# Sheet1.net
KiCad netlist of a schematic drawn in Altium Designer
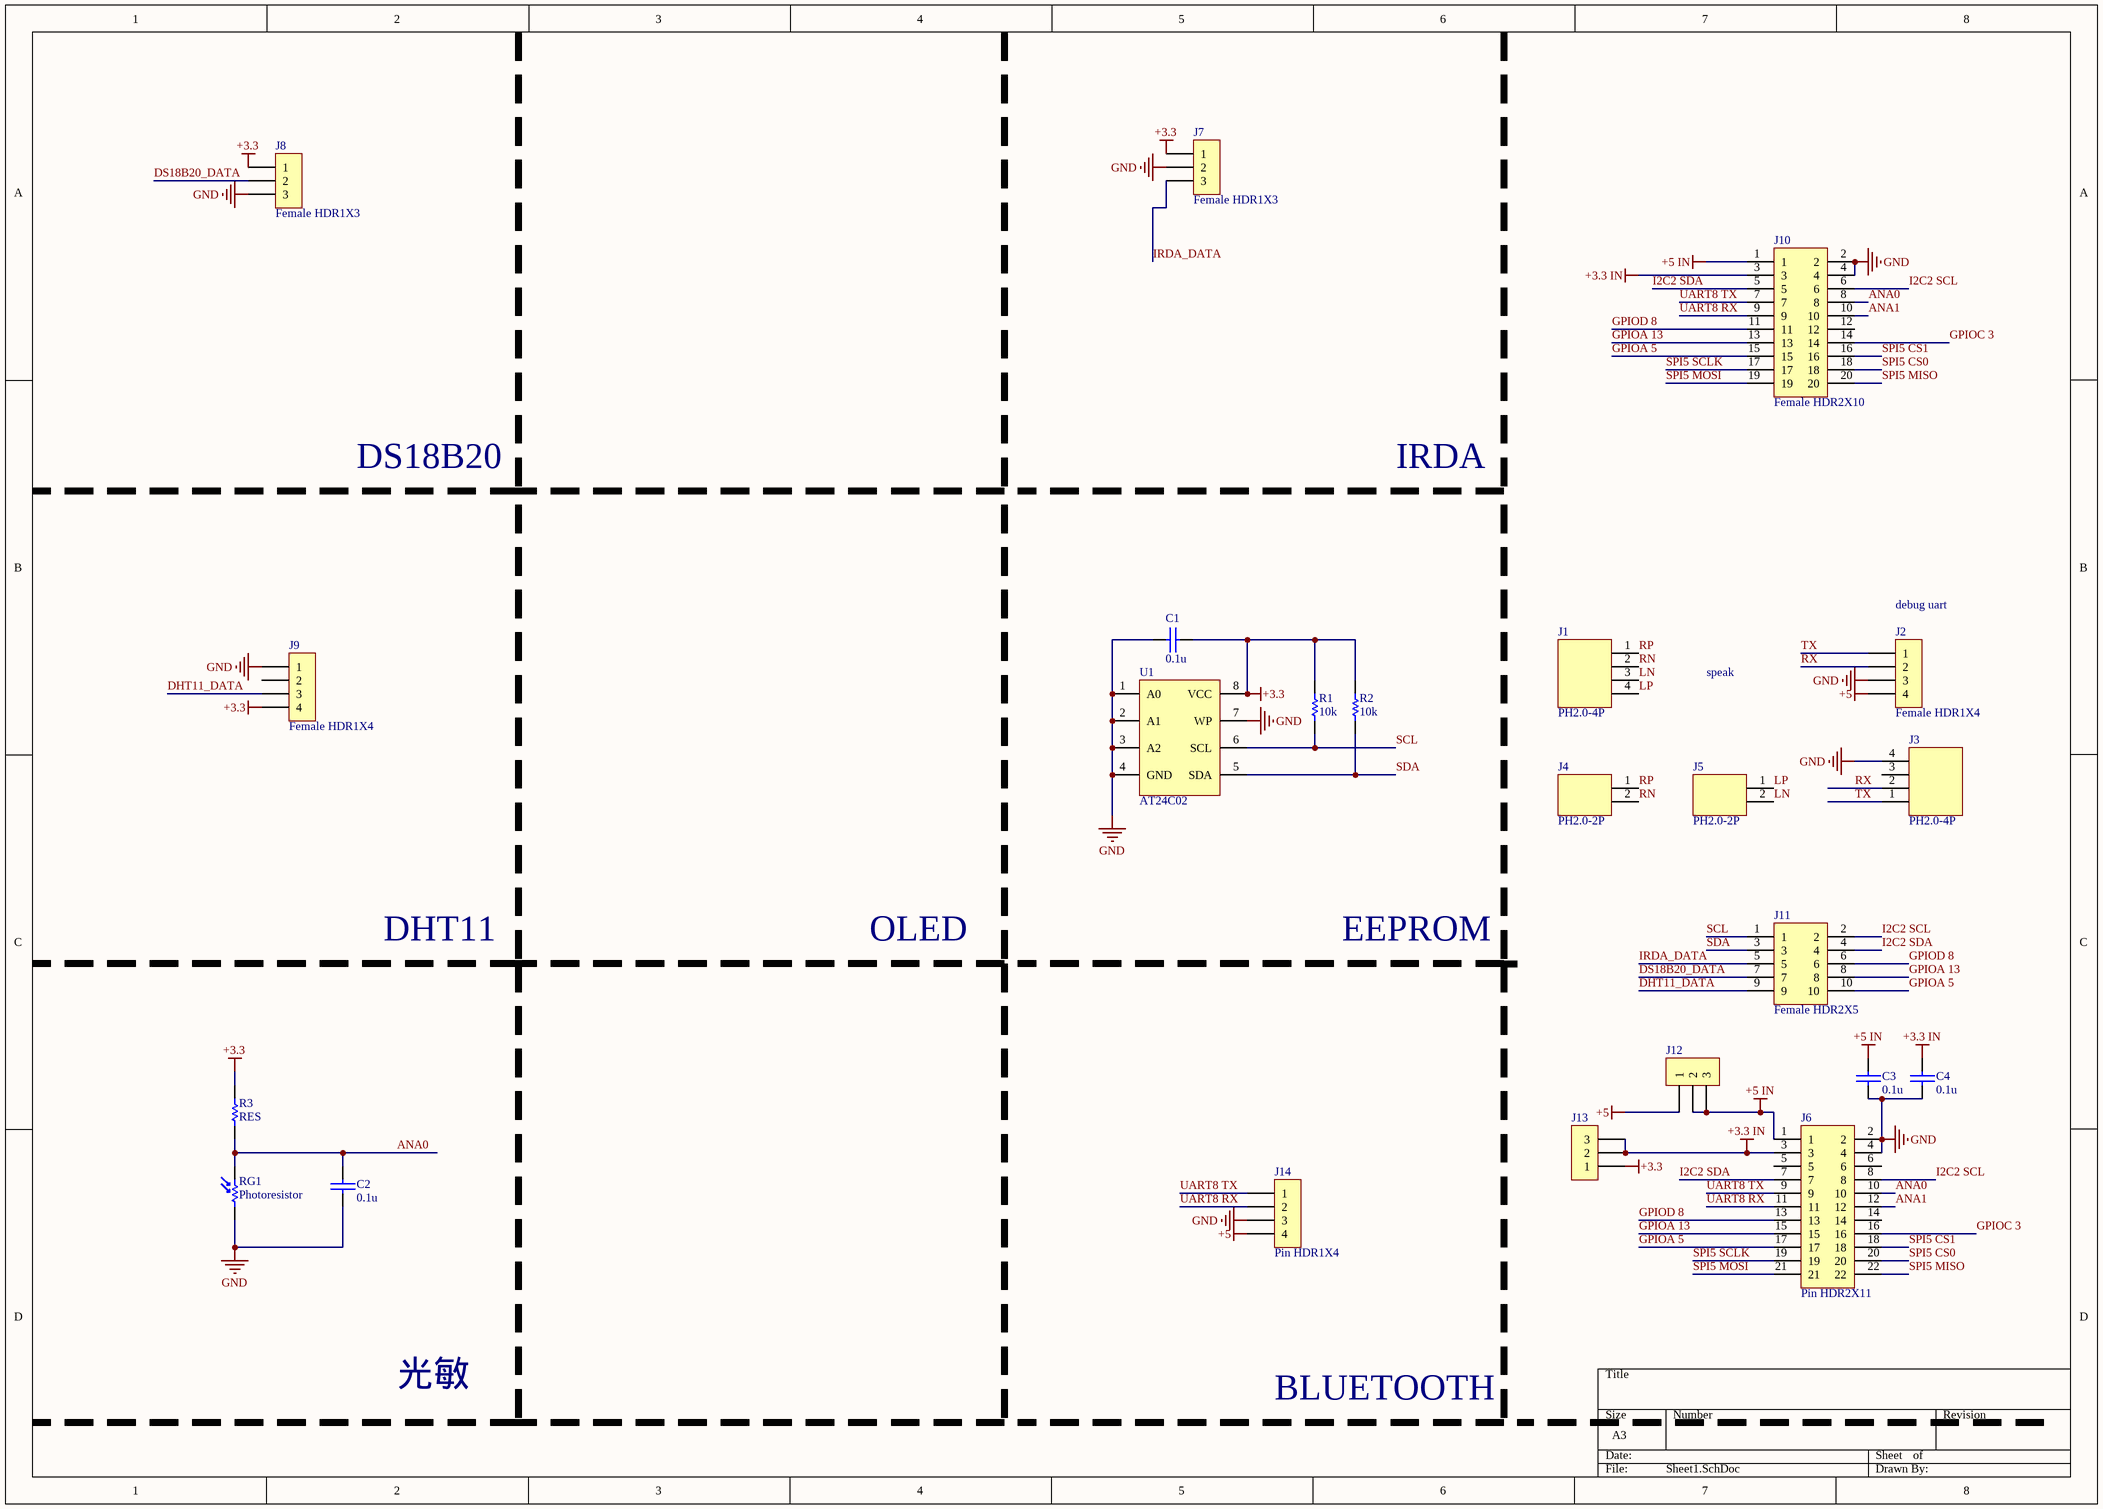
[diagram p0: Sheet1.SchDoc]

(export (version "E")
  (design (tool "Eeschema 10.0.6"))
  (components
    (comp (ref "C1")
      (value "0.1u")
      (footprint "0805C")
      (description "无极性电容")
      (libsource (lib "常用元件-电容") (part "CAP"))
    )
    (comp (ref "C2")
      (value "0.1u")
      (footprint "0805C")
      (description "无极性电容")
      (libsource (lib "常用元件-电容") (part "CAP"))
    )
    (comp (ref "C3")
      (value "0.1u")
      (footprint "0805C")
      (description "无极性电容")
      (libsource (lib "常用元件-电容") (part "CAP"))
    )
    (comp (ref "C4")
      (value "0.1u")
      (footprint "0805C")
      (description "无极性电容")
      (libsource (lib "常用元件-电容") (part "CAP"))
    )
    (comp (ref "J1") (value "PH2.0-4P") (footprint "PH2.0-4P") (libsource (lib "") (part "PH2.0-4P_1")))
    (comp (ref "J2")
      (value "Female HDR1X4")
      (footprint "Fe-HDR1X4/2.54-S")
      (libsource (lib "常用元件-排母") (part "Female HDR1X4"))
    )
    (comp (ref "J3") (value "PH2.0-4P") (footprint "PH2.0-4P") (libsource (lib "插接类-PH") (part "PH2.0-4P")))
    (comp (ref "J4") (value "PH2.0-2P") (footprint "PH2.0-2P") (libsource (lib "插接类-PH") (part "PH2.0-2P")))
    (comp (ref "J5") (value "PH2.0-2P") (footprint "PH2.0-2P") (libsource (lib "插接类-PH") (part "PH2.0-2P")))
    (comp (ref "J6")
      (value "Pin HDR2X11")
      (footprint "HDR-TH_22P-P2.00-V-F-R2-C11-S2.00")
      (libsource (lib "常用元件-排针") (part "Pin HDR2X11"))
    )
    (comp (ref "J7")
      (value "Female HDR1X3")
      (footprint "Fe-HDR1X3/2.54-S")
      (libsource (lib "") (part "Female HDR1X3_1"))
    )
    (comp (ref "J8")
      (value "Female HDR1X3")
      (footprint "Fe-HDR1X3/2.54-S")
      (libsource (lib "") (part "Female HDR1X3_1"))
    )
    (comp (ref "J9")
      (value "Female HDR1X4")
      (footprint "Fe-HDR1X4/2.54-S")
      (libsource (lib "常用元件-排母") (part "Female HDR1X4"))
    )
    (comp (ref "J10")
      (value "Female HDR2X10")
      (footprint "Fe-HDR2X10/2.54-S")
      (libsource (lib "常用元件-排母") (part "Female HDR2X10"))
    )
    (comp (ref "J11")
      (value "Female HDR2X5")
      (footprint "Fe-HDR2X5/2.54-S")
      (libsource (lib "常用元件-排母") (part "Female HDR2X5"))
    )
    (comp (ref "J12")
      (value "Female HDR1X3")
      (footprint "Fe-HDR1X3/2.54-S")
      (libsource (lib "") (part "Female HDR1X3_2"))
    )
    (comp (ref "J13")
      (value "Female HDR1X3")
      (footprint "Fe-HDR1X3/2.54-S")
      (libsource (lib "常用元件-排母") (part "Female HDR1X3"))
    )
    (comp (ref "J14")
      (value "Pin HDR1X4")
      (footprint "Pin HDR1X4/2.54mm-S")
      (libsource (lib "常用元件-排针") (part "Pin HDR1X4"))
    )
    (comp (ref "R1") (value "10k") (footprint "0805R") (libsource (lib "常用元件-电阻") (part "RES")))
    (comp (ref "R2") (value "10k") (footprint "0805R") (libsource (lib "常用元件-电阻") (part "RES")))
    (comp (ref "R3") (value "RES") (footprint "0805R") (libsource (lib "常用元件-电阻") (part "RES")))
    (comp (ref "RG1")
      (value "Photoresistor")
      (footprint "Photoresistor")
      (description "光敏电阻")
      (libsource (lib "常用元件-电阻") (part "Photoresistor"))
    )
    (comp (ref "U1") (value "AT24C02") (footprint "SOP8") (libsource (lib "芯片-未分类IC") (part "AT24C02")))
  )
  (nets
    (net (code "1") (name "+3.3") (class "Default")
      (node (ref "C1") (pin "2") (pinfunction "2_2") (pintype "passive"))
      (node (ref "J13") (pin "1") (pinfunction "1_1") (pintype "passive"))
      (node (ref "J7") (pin "1") (pinfunction "1_1") (pintype "passive"))
      (node (ref "J8") (pin "1") (pinfunction "1_1") (pintype "passive"))
      (node (ref "J9") (pin "4") (pinfunction "4_4") (pintype "passive"))
      (node (ref "R1") (pin "2") (pinfunction "2_2") (pintype "passive"))
      (node (ref "R2") (pin "2") (pinfunction "2_2") (pintype "passive"))
      (node (ref "R3") (pin "2") (pinfunction "2_2") (pintype "passive"))
      (node (ref "U1") (pin "8") (pinfunction "VCC_8") (pintype "passive"))
    )
    (net (code "2") (name "+3.3 IN") (class "Default")
      (node (ref "C4") (pin "2") (pinfunction "2_2") (pintype "passive"))
      (node (ref "J10") (pin "3") (pinfunction "3_3") (pintype "passive"))
      (node (ref "J13") (pin "2") (pinfunction "2_2") (pintype "passive"))
      (node (ref "J13") (pin "3") (pinfunction "3_3") (pintype "passive"))
      (node (ref "J6") (pin "3") (pinfunction "3_3") (pintype "passive"))
    )
    (net (code "3") (name "+5") (class "Default")
      (node (ref "J12") (pin "1") (pinfunction "1_1") (pintype "passive"))
      (node (ref "J14") (pin "4") (pinfunction "4_4") (pintype "passive"))
      (node (ref "J2") (pin "4") (pinfunction "4_4") (pintype "passive"))
    )
    (net (code "4") (name "+5 IN") (class "Default")
      (node (ref "C3") (pin "2") (pinfunction "2_2") (pintype "passive"))
      (node (ref "J10") (pin "1") (pinfunction "1_1") (pintype "passive"))
      (node (ref "J12") (pin "2") (pinfunction "2_2") (pintype "passive"))
      (node (ref "J12") (pin "3") (pinfunction "3_3") (pintype "passive"))
      (node (ref "J6") (pin "1") (pinfunction "1_1") (pintype "passive"))
    )
    (net (code "5") (name "/ANA0") (class "Default")
      (node (ref "C2") (pin "2") (pinfunction "2_2") (pintype "passive"))
      (node (ref "J10") (pin "8") (pinfunction "8_8") (pintype "passive"))
      (node (ref "J6") (pin "10") (pinfunction "10_10") (pintype "passive"))
      (node (ref "R3") (pin "1") (pinfunction "1_1") (pintype "passive"))
      (node (ref "RG1") (pin "2") (pinfunction "2_2") (pintype "passive"))
    )
    (net (code "6") (name "/ANA1") (class "Default")
      (node (ref "J10") (pin "10") (pinfunction "10_10") (pintype "passive"))
      (node (ref "J6") (pin "12") (pinfunction "12_12") (pintype "passive"))
    )
    (net (code "7") (name "/DHT11_DATA") (class "Default")
      (node (ref "J11") (pin "9") (pinfunction "9_9") (pintype "passive"))
      (node (ref "J9") (pin "3") (pinfunction "3_3") (pintype "passive"))
    )
    (net (code "8") (name "/DS18B20_DATA") (class "Default")
      (node (ref "J11") (pin "7") (pinfunction "7_7") (pintype "passive"))
      (node (ref "J8") (pin "2") (pinfunction "2_2") (pintype "passive"))
    )
    (net (code "9") (name "/GPIOA 5") (class "Default")
      (node (ref "J10") (pin "15") (pinfunction "15_15") (pintype "passive"))
      (node (ref "J11") (pin "10") (pinfunction "10_10") (pintype "passive"))
      (node (ref "J6") (pin "17") (pinfunction "17_17") (pintype "passive"))
    )
    (net (code "10") (name "/GPIOA 13") (class "Default")
      (node (ref "J10") (pin "13") (pinfunction "13_13") (pintype "passive"))
      (node (ref "J11") (pin "8") (pinfunction "8_8") (pintype "passive"))
      (node (ref "J6") (pin "15") (pinfunction "15_15") (pintype "passive"))
    )
    (net (code "11") (name "/GPIOC 3") (class "Default")
      (node (ref "J10") (pin "14") (pinfunction "14_14") (pintype "passive"))
      (node (ref "J6") (pin "16") (pinfunction "16_16") (pintype "passive"))
    )
    (net (code "12") (name "/GPIOD 8") (class "Default")
      (node (ref "J10") (pin "11") (pinfunction "11_11") (pintype "passive"))
      (node (ref "J11") (pin "6") (pinfunction "6_6") (pintype "passive"))
      (node (ref "J6") (pin "13") (pinfunction "13_13") (pintype "passive"))
    )
    (net (code "13") (name "/I2C2 SCL") (class "Default")
      (node (ref "J10") (pin "6") (pinfunction "6_6") (pintype "passive"))
      (node (ref "J11") (pin "2") (pinfunction "2_2") (pintype "passive"))
      (node (ref "J6") (pin "8") (pinfunction "8_8") (pintype "passive"))
    )
    (net (code "14") (name "/I2C2 SDA") (class "Default")
      (node (ref "J10") (pin "5") (pinfunction "5_5") (pintype "passive"))
      (node (ref "J11") (pin "4") (pinfunction "4_4") (pintype "passive"))
      (node (ref "J6") (pin "7") (pinfunction "7_7") (pintype "passive"))
    )
    (net (code "15") (name "/IRDA_DATA") (class "Default")
      (node (ref "J11") (pin "5") (pinfunction "5_5") (pintype "passive"))
      (node (ref "J7") (pin "3") (pinfunction "3_3") (pintype "passive"))
    )
    (net (code "16") (name "/LN") (class "Default")
      (node (ref "J1") (pin "3") (pinfunction "3_3") (pintype "passive"))
      (node (ref "J5") (pin "2") (pinfunction "2_2") (pintype "passive"))
    )
    (net (code "17") (name "/LP") (class "Default")
      (node (ref "J1") (pin "4") (pinfunction "4_4") (pintype "passive"))
      (node (ref "J5") (pin "1") (pinfunction "1_1") (pintype "passive"))
    )
    (net (code "18") (name "/RN") (class "Default")
      (node (ref "J1") (pin "2") (pinfunction "2_2") (pintype "passive"))
      (node (ref "J4") (pin "2") (pinfunction "2_2") (pintype "passive"))
    )
    (net (code "19") (name "/RP") (class "Default")
      (node (ref "J1") (pin "1") (pinfunction "1_1") (pintype "passive"))
      (node (ref "J4") (pin "1") (pinfunction "1_1") (pintype "passive"))
    )
    (net (code "20") (name "/RX") (class "Default")
      (node (ref "J2") (pin "2") (pinfunction "2_2") (pintype "passive"))
      (node (ref "J3") (pin "2") (pinfunction "2_2") (pintype "passive"))
    )
    (net (code "21") (name "/SCL") (class "Default")
      (node (ref "J11") (pin "1") (pinfunction "1_1") (pintype "passive"))
      (node (ref "R1") (pin "1") (pinfunction "1_1") (pintype "passive"))
      (node (ref "U1") (pin "6") (pinfunction "SCL_6") (pintype "passive"))
    )
    (net (code "22") (name "/SDA") (class "Default")
      (node (ref "J11") (pin "3") (pinfunction "3_3") (pintype "passive"))
      (node (ref "R2") (pin "1") (pinfunction "1_1") (pintype "passive"))
      (node (ref "U1") (pin "5") (pinfunction "SDA_5") (pintype "passive"))
    )
    (net (code "23") (name "/SPI5 CS0") (class "Default")
      (node (ref "J10") (pin "18") (pinfunction "18_18") (pintype "passive"))
      (node (ref "J6") (pin "20") (pinfunction "20_20") (pintype "passive"))
    )
    (net (code "24") (name "/SPI5 CS1") (class "Default")
      (node (ref "J10") (pin "16") (pinfunction "16_16") (pintype "passive"))
      (node (ref "J6") (pin "18") (pinfunction "18_18") (pintype "passive"))
    )
    (net (code "25") (name "/SPI5 MISO") (class "Default")
      (node (ref "J10") (pin "20") (pinfunction "20_20") (pintype "passive"))
      (node (ref "J6") (pin "22") (pinfunction "22_22") (pintype "passive"))
    )
    (net (code "26") (name "/SPI5 MOSI") (class "Default")
      (node (ref "J10") (pin "19") (pinfunction "19_19") (pintype "passive"))
      (node (ref "J6") (pin "21") (pinfunction "21_21") (pintype "passive"))
    )
    (net (code "27") (name "/SPI5 SCLK") (class "Default")
      (node (ref "J10") (pin "17") (pinfunction "17_17") (pintype "passive"))
      (node (ref "J6") (pin "19") (pinfunction "19_19") (pintype "passive"))
    )
    (net (code "28") (name "/TX") (class "Default")
      (node (ref "J2") (pin "1") (pinfunction "1_1") (pintype "passive"))
      (node (ref "J3") (pin "1") (pinfunction "1_1") (pintype "passive"))
    )
    (net (code "29") (name "/UART8 RX") (class "Default")
      (node (ref "J10") (pin "9") (pinfunction "9_9") (pintype "passive"))
      (node (ref "J14") (pin "2") (pinfunction "2_2") (pintype "passive"))
      (node (ref "J6") (pin "11") (pinfunction "11_11") (pintype "passive"))
    )
    (net (code "30") (name "/UART8 TX") (class "Default")
      (node (ref "J10") (pin "7") (pinfunction "7_7") (pintype "passive"))
      (node (ref "J14") (pin "1") (pinfunction "1_1") (pintype "passive"))
      (node (ref "J6") (pin "9") (pinfunction "9_9") (pintype "passive"))
    )
    (net (code "31") (name "GND") (class "Default")
      (node (ref "C1") (pin "1") (pinfunction "1_1") (pintype "passive"))
      (node (ref "C2") (pin "1") (pinfunction "1_1") (pintype "passive"))
      (node (ref "C3") (pin "1") (pinfunction "1_1") (pintype "passive"))
      (node (ref "C4") (pin "1") (pinfunction "1_1") (pintype "passive"))
      (node (ref "J10") (pin "2") (pinfunction "2_2") (pintype "passive"))
      (node (ref "J10") (pin "4") (pinfunction "4_4") (pintype "passive"))
      (node (ref "J14") (pin "3") (pinfunction "3_3") (pintype "passive"))
      (node (ref "J2") (pin "3") (pinfunction "3_3") (pintype "passive"))
      (node (ref "J3") (pin "4") (pinfunction "4_4") (pintype "passive"))
      (node (ref "J6") (pin "2") (pinfunction "2_2") (pintype "passive"))
      (node (ref "J6") (pin "4") (pinfunction "4_4") (pintype "passive"))
      (node (ref "J7") (pin "2") (pinfunction "2_2") (pintype "passive"))
      (node (ref "J8") (pin "3") (pinfunction "3_3") (pintype "passive"))
      (node (ref "J9") (pin "1") (pinfunction "1_1") (pintype "passive"))
      (node (ref "RG1") (pin "1") (pinfunction "1_1") (pintype "passive"))
      (node (ref "U1") (pin "1") (pinfunction "A0_1") (pintype "passive"))
      (node (ref "U1") (pin "2") (pinfunction "A1_2") (pintype "passive"))
      (node (ref "U1") (pin "3") (pinfunction "A2_3") (pintype "passive"))
      (node (ref "U1") (pin "4") (pinfunction "GND_4") (pintype "passive"))
      (node (ref "U1") (pin "7") (pinfunction "WP_7") (pintype "passive"))
    )
    (net (code "32") (name "unconnected-(J3-Pad3)") (class "Default")
      (node (ref "J3") (pin "3") (pinfunction "3_3") (pintype "passive"))
    )
    (net (code "33") (name "unconnected-(J6-Pad5)") (class "Default")
      (node (ref "J6") (pin "5") (pinfunction "5_5") (pintype "passive"))
    )
    (net (code "34") (name "unconnected-(J6-Pad6)") (class "Default")
      (node (ref "J6") (pin "6") (pinfunction "6_6") (pintype "passive"))
    )
    (net (code "35") (name "unconnected-(J6-Pad14)") (class "Default")
      (node (ref "J6") (pin "14") (pinfunction "14_14") (pintype "passive"))
    )
    (net (code "36") (name "unconnected-(J9-Pad2)") (class "Default")
      (node (ref "J9") (pin "2") (pinfunction "2_2") (pintype "passive"))
    )
    (net (code "37") (name "unconnected-(J10-Pad12)") (class "Default")
      (node (ref "J10") (pin "12") (pinfunction "12_12") (pintype "passive"))
    )
  )
)
